# STM32F103ZET6.net
KiCad netlist of a schematic drawn in Altium Designer
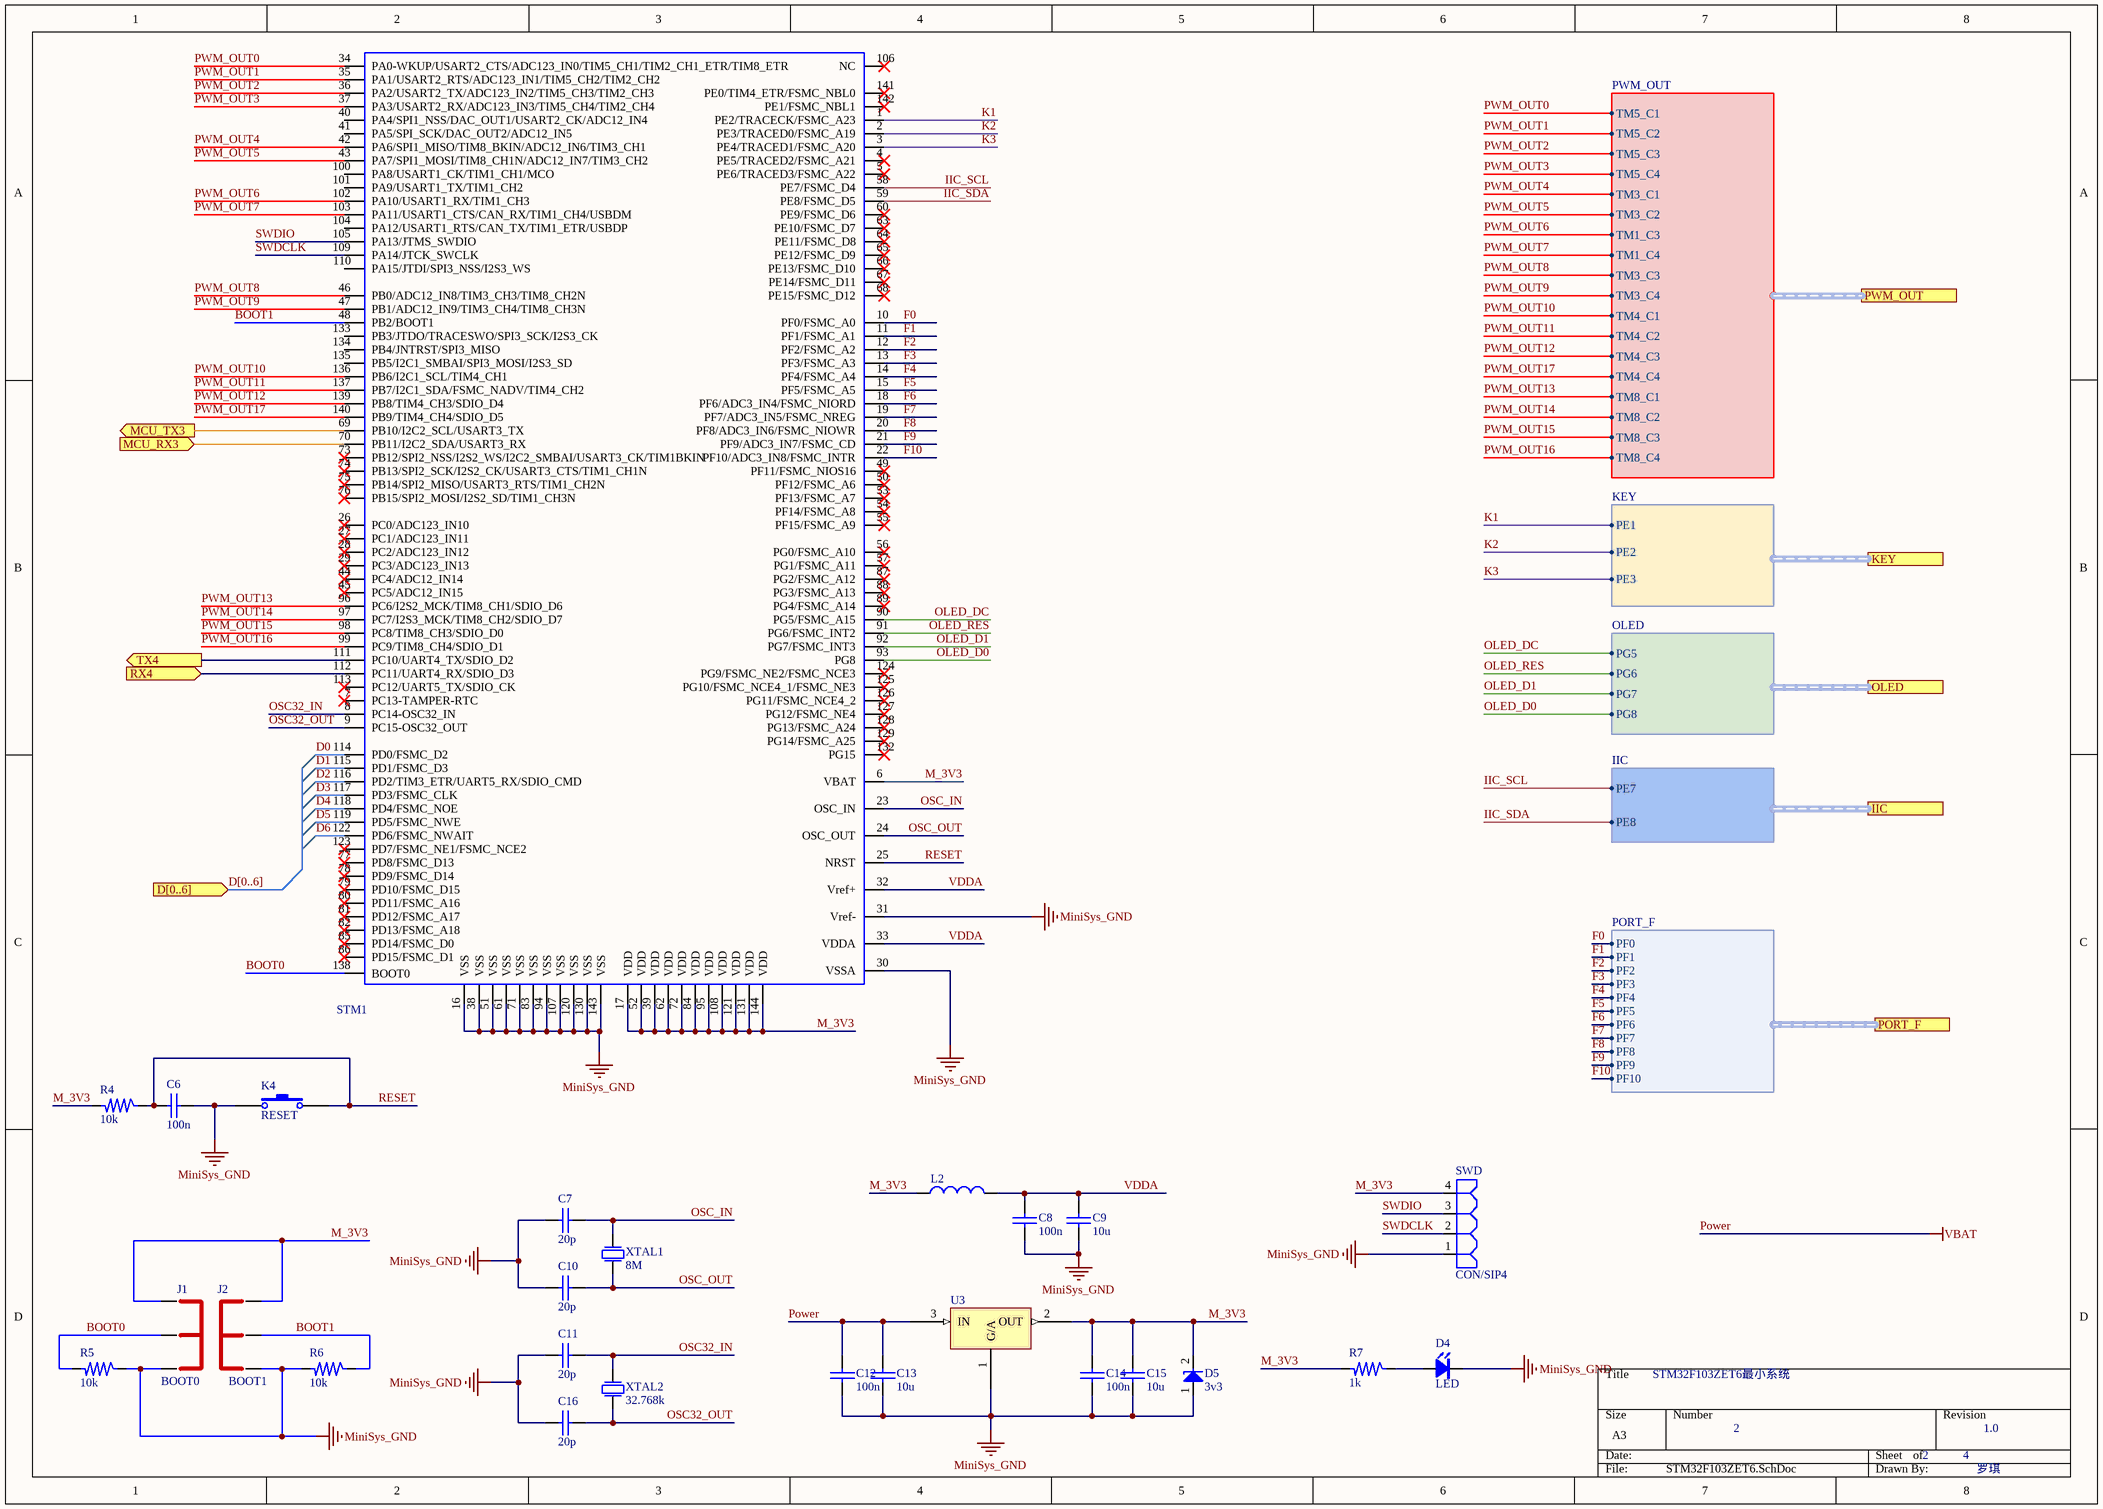
[diagram p0: STM32F103ZET6.SchDoc]

(export (version "E")
  (design (tool "Eeschema 10.0.6"))
  (components
    (comp (ref "C6")
      (value "100n")
      (footprint "C0402")
      (description "电容")
      (libsource (lib "LQ_Integrated_Library") (part "Capacitor"))
    )
    (comp (ref "C7")
      (value "20p")
      (footprint "C0402")
      (description "电容")
      (libsource (lib "LQ_Integrated_Library") (part "Capacitor"))
    )
    (comp (ref "C8")
      (value "100n")
      (footprint "C0402")
      (description "电容")
      (libsource (lib "LQ_Integrated_Library") (part "Capacitor"))
    )
    (comp (ref "C9")
      (value "10u")
      (footprint "C0402")
      (description "电容")
      (libsource (lib "LQ_Integrated_Library") (part "Capacitor"))
    )
    (comp (ref "C10")
      (value "20p")
      (footprint "C0402")
      (description "电容")
      (libsource (lib "LQ_Integrated_Library") (part "Capacitor"))
    )
    (comp (ref "C11")
      (value "20p")
      (footprint "C0402")
      (description "电容")
      (libsource (lib "LQ_Integrated_Library") (part "Capacitor"))
    )
    (comp (ref "C12")
      (value "100n")
      (footprint "C0402")
      (description "电容")
      (libsource (lib "LQ_Integrated_Library") (part "Capacitor"))
    )
    (comp (ref "C13")
      (value "10u")
      (footprint "C0402")
      (description "电容")
      (libsource (lib "LQ_Integrated_Library") (part "Capacitor"))
    )
    (comp (ref "C14")
      (value "100n")
      (footprint "C0402")
      (description "电容")
      (libsource (lib "LQ_Integrated_Library") (part "Capacitor"))
    )
    (comp (ref "C15")
      (value "10u")
      (footprint "C0402")
      (description "电容")
      (libsource (lib "LQ_Integrated_Library") (part "Capacitor"))
    )
    (comp (ref "C16")
      (value "20p")
      (footprint "C0402")
      (description "电容")
      (libsource (lib "LQ_Integrated_Library") (part "Capacitor"))
    )
    (comp (ref "D4")
      (value "LED")
      (footprint "LED0805TB")
      (libsource (lib "LQ_Integrated_Library") (part "LED"))
    )
    (comp (ref "D5")
      (value "3v3")
      (footprint "D1206")
      (libsource (lib "LQ_Integrated_Library") (part "DIODE稳压"))
    )
    (comp (ref "J1")
      (value "BOOT0")
      (footprint "Jumper3")
      (description "Jumper")
      (libsource (lib "LQ_Integrated_Library") (part "JUMPER3"))
    )
    (comp (ref "J2")
      (value "BOOT1")
      (footprint "Jumper3")
      (description "Jumper")
      (libsource (lib "LQ_Integrated_Library") (part "JUMPER3"))
    )
    (comp (ref "K4") (value "RESET") (footprint "按键-贴片-1") (libsource (lib "APPPCB") (part "按键")))
    (comp (ref "L2")
      (value "INDUCTOR")
      (footprint "L0805")
      (description "Inductor")
      (libsource (lib "LQ_Integrated_Library") (part "INDUCTOR"))
    )
    (comp (ref "R4")
      (value "10k")
      (footprint "R0805")
      (description "电阻")
      (libsource (lib "LQ_Integrated_Library") (part "Resistor"))
    )
    (comp (ref "R5")
      (value "10k")
      (footprint "R0805")
      (description "电阻")
      (libsource (lib "LQ_Integrated_Library") (part "Resistor"))
    )
    (comp (ref "R6")
      (value "10k")
      (footprint "R0805")
      (description "电阻")
      (libsource (lib "LQ_Integrated_Library") (part "Resistor"))
    )
    (comp (ref "R7")
      (value "1k")
      (footprint "R0805")
      (description "电阻")
      (libsource (lib "LQ_Integrated_Library") (part "Resistor"))
    )
    (comp (ref "STM1")
      (value "STM32F103ZET6")
      (footprint "STM32F103ZET6-1")
      (libsource (lib "APPPCB") (part "STM32F103ZET6"))
    )
    (comp (ref "SWD")
      (value "CON/SIP4")
      (footprint "HDR1X4")
      (libsource (lib "LQ_Integrated_Library") (part "CON/SIP4"))
    )
    (comp (ref "U3")
      (value "AMS1117-XX")
      (footprint "SOT223")
      (description "稳压芯片")
      (libsource (lib "LQ_Integrated_Library") (part "AMS1117-XX"))
    )
    (comp (ref "XTAL1")
      (value "8M")
      (footprint "XTAL-49/S_N")
      (description "CRYSTAL")
      (libsource (lib "LQ_Integrated_Library") (part "XTAL"))
    )
    (comp (ref "XTAL2")
      (value "32.768k")
      (footprint "XTAL_32.768")
      (description "CRYSTAL")
      (libsource (lib "LQ_Integrated_Library") (part "XTAL"))
    )
  )
  (nets
    (net (code "6") (name "/BOOT0") (class "Default")
      (node (ref "J1") (pin "2") (pinfunction "2_2") (pintype "passive"))
      (node (ref "R5") (pin "1") (pinfunction "1_1") (pintype "passive"))
      (node (ref "STM1") (pin "138") (pinfunction "BOOT0_138") (pintype "passive"))
    )
    (net (code "7") (name "/BOOT1") (class "Default")
      (node (ref "J2") (pin "2") (pinfunction "2_2") (pintype "passive"))
      (node (ref "R6") (pin "2") (pinfunction "2_2") (pintype "passive"))
      (node (ref "STM1") (pin "48") (pinfunction "PB2/BOOT1_48") (pintype "passive"))
    )
    (net (code "8") (name "/D0") (class "Default")
      (node (ref "STM1") (pin "114") (pinfunction "PD0/FSMC_D2_114") (pintype "passive"))
    )
    (net (code "9") (name "/D1") (class "Default")
      (node (ref "STM1") (pin "115") (pinfunction "PD1/FSMC_D3_115") (pintype "passive"))
    )
    (net (code "10") (name "/D2") (class "Default")
      (node (ref "STM1") (pin "116") (pinfunction "PD2/TIM3_ETR/UART5_RX/SDIO_CMD_116") (pintype "passive"))
    )
    (net (code "11") (name "/D3") (class "Default")
      (node (ref "STM1") (pin "117") (pinfunction "PD3/FSMC_CLK_117") (pintype "passive"))
    )
    (net (code "12") (name "/D4") (class "Default")
      (node (ref "STM1") (pin "118") (pinfunction "PD4/FSMC_NOE_118") (pintype "passive"))
    )
    (net (code "13") (name "/D5") (class "Default")
      (node (ref "STM1") (pin "119") (pinfunction "PD5/FSMC_NWE_119") (pintype "passive"))
    )
    (net (code "14") (name "/D6") (class "Default")
      (node (ref "STM1") (pin "122") (pinfunction "PD6/FSMC_NWAIT_122") (pintype "passive"))
    )
    (net (code "16") (name "/F0") (class "Default")
      (node (ref "STM1") (pin "10") (pinfunction "PF0/FSMC_A0_10") (pintype "passive"))
    )
    (net (code "17") (name "/F1") (class "Default")
      (node (ref "STM1") (pin "11") (pinfunction "PF1/FSMC_A1_11") (pintype "passive"))
    )
    (net (code "18") (name "/F2") (class "Default")
      (node (ref "STM1") (pin "12") (pinfunction "PF2/FSMC_A2_12") (pintype "passive"))
    )
    (net (code "19") (name "/F3") (class "Default")
      (node (ref "STM1") (pin "13") (pinfunction "PF3/FSMC_A3_13") (pintype "passive"))
    )
    (net (code "20") (name "/F4") (class "Default")
      (node (ref "STM1") (pin "14") (pinfunction "PF4/FSMC_A4_14") (pintype "passive"))
    )
    (net (code "21") (name "/F5") (class "Default")
      (node (ref "STM1") (pin "15") (pinfunction "PF5/FSMC_A5_15") (pintype "passive"))
    )
    (net (code "22") (name "/F6") (class "Default")
      (node (ref "STM1") (pin "18") (pinfunction "PF6/ADC3_IN4/FSMC_NIORD_18") (pintype "passive"))
    )
    (net (code "23") (name "/F7") (class "Default")
      (node (ref "STM1") (pin "19") (pinfunction "PF7/ADC3_IN5/FSMC_NREG_19") (pintype "passive"))
    )
    (net (code "24") (name "/F8") (class "Default")
      (node (ref "STM1") (pin "20") (pinfunction "PF8/ADC3_IN6/FSMC_NIOWR_20") (pintype "passive"))
    )
    (net (code "25") (name "/F9") (class "Default")
      (node (ref "STM1") (pin "21") (pinfunction "PF9/ADC3_IN7/FSMC_CD_21") (pintype "passive"))
    )
    (net (code "26") (name "/F10") (class "Default")
      (node (ref "STM1") (pin "22") (pinfunction "PF10/ADC3_IN8/FSMC_INTR_22") (pintype "passive"))
    )
    (net (code "27") (name "/IIC_SCL") (class "Default")
      (node (ref "STM1") (pin "58") (pinfunction "PE7/FSMC_D4_58") (pintype "passive"))
    )
    (net (code "28") (name "/IIC_SDA") (class "Default")
      (node (ref "STM1") (pin "59") (pinfunction "PE8/FSMC_D5_59") (pintype "passive"))
    )
    (net (code "29") (name "/K1") (class "Default")
      (node (ref "STM1") (pin "1") (pinfunction "PE2/TRACECK/FSMC_A23_1") (pintype "passive"))
    )
    (net (code "30") (name "/K2") (class "Default")
      (node (ref "STM1") (pin "2") (pinfunction "PE3/TRACED0/FSMC_A19_2") (pintype "passive"))
    )
    (net (code "31") (name "/K3") (class "Default")
      (node (ref "STM1") (pin "3") (pinfunction "PE4/TRACED1/FSMC_A20_3") (pintype "passive"))
    )
    (net (code "32") (name "/MCU_RX3") (class "Default")
      (node (ref "STM1") (pin "70") (pinfunction "PB11/I2C2_SDA/USART3_RX_70") (pintype "passive"))
    )
    (net (code "33") (name "/MCU_TX3") (class "Default")
      (node (ref "STM1") (pin "69") (pinfunction "PB10/I2C2_SCL/USART3_TX_69") (pintype "passive"))
    )
    (net (code "34") (name "/M_3V3") (class "Default")
      (node (ref "C14") (pin "2") (pinfunction "2_2") (pintype "passive"))
      (node (ref "C15") (pin "2") (pinfunction "2_2") (pintype "passive"))
      (node (ref "D5") (pin "2") (pintype "passive"))
      (node (ref "J1") (pin "1") (pinfunction "1_1") (pintype "passive"))
      (node (ref "J2") (pin "3") (pinfunction "3_3") (pintype "passive"))
      (node (ref "L2") (pin "1") (pinfunction "1_1") (pintype "passive"))
      (node (ref "R4") (pin "1") (pinfunction "1_1") (pintype "passive"))
      (node (ref "R7") (pin "1") (pinfunction "1_1") (pintype "passive"))
      (node (ref "STM1") (pin "108") (pinfunction "VDD_108") (pintype "passive"))
      (node (ref "STM1") (pin "121") (pinfunction "VDD_121") (pintype "passive"))
      (node (ref "STM1") (pin "131") (pinfunction "VDD_131") (pintype "passive"))
      (node (ref "STM1") (pin "144") (pinfunction "VDD_144") (pintype "passive"))
      (node (ref "STM1") (pin "17") (pinfunction "VDD_17") (pintype "passive"))
      (node (ref "STM1") (pin "39") (pinfunction "VDD_39") (pintype "passive"))
      (node (ref "STM1") (pin "52") (pinfunction "VDD_52") (pintype "passive"))
      (node (ref "STM1") (pin "6") (pinfunction "VBAT_6") (pintype "passive"))
      (node (ref "STM1") (pin "62") (pinfunction "VDD_62") (pintype "passive"))
      (node (ref "STM1") (pin "72") (pinfunction "VDD_72") (pintype "passive"))
      (node (ref "STM1") (pin "84") (pinfunction "VDD_84") (pintype "passive"))
      (node (ref "STM1") (pin "95") (pinfunction "VDD_95") (pintype "passive"))
      (node (ref "SWD") (pin "4") (pintype "passive"))
      (node (ref "U3") (pin "2") (pinfunction "OUT_2") (pintype "output"))
    )
    (net (code "35") (name "/OLED_D0") (class "Default")
      (node (ref "STM1") (pin "93") (pinfunction "PG8_93") (pintype "passive"))
    )
    (net (code "36") (name "/OLED_D1") (class "Default")
      (node (ref "STM1") (pin "92") (pinfunction "PG7/FSMC_INT3_92") (pintype "passive"))
    )
    (net (code "37") (name "/OLED_DC") (class "Default")
      (node (ref "STM1") (pin "90") (pinfunction "PG5/FSMC_A15_90") (pintype "passive"))
    )
    (net (code "38") (name "/OLED_RES") (class "Default")
      (node (ref "STM1") (pin "91") (pinfunction "PG6/FSMC_INT2_91") (pintype "passive"))
    )
    (net (code "39") (name "/OSC32_IN") (class "Default")
      (node (ref "C11") (pin "2") (pinfunction "2_2") (pintype "passive"))
      (node (ref "STM1") (pin "8") (pinfunction "PC14-OSC32_IN_8") (pintype "passive"))
      (node (ref "XTAL2") (pin "1") (pinfunction "P1_1") (pintype "passive"))
    )
    (net (code "40") (name "/OSC32_OUT") (class "Default")
      (node (ref "C16") (pin "2") (pinfunction "2_2") (pintype "passive"))
      (node (ref "STM1") (pin "9") (pinfunction "PC15-OSC32_OUT_9") (pintype "passive"))
      (node (ref "XTAL2") (pin "2") (pinfunction "P2_2") (pintype "passive"))
    )
    (net (code "41") (name "/OSC_IN") (class "Default")
      (node (ref "C7") (pin "2") (pinfunction "2_2") (pintype "passive"))
      (node (ref "STM1") (pin "23") (pinfunction "OSC_IN_23") (pintype "passive"))
      (node (ref "XTAL1") (pin "1") (pinfunction "P1_1") (pintype "passive"))
    )
    (net (code "42") (name "/OSC_OUT") (class "Default")
      (node (ref "C10") (pin "2") (pinfunction "2_2") (pintype "passive"))
      (node (ref "STM1") (pin "24") (pinfunction "OSC_OUT_24") (pintype "passive"))
      (node (ref "XTAL1") (pin "2") (pinfunction "P2_2") (pintype "passive"))
    )
    (net (code "43") (name "/PWM_OUT0") (class "Default")
      (node (ref "STM1") (pin "34") (pinfunction "PA0-WKUP/USART2_CTS/ADC123_IN0/TIM5_CH1/TIM2_CH1_ETR/TIM8_ETR_34") (pintype "passive"))
    )
    (net (code "44") (name "/PWM_OUT1") (class "Default")
      (node (ref "STM1") (pin "35") (pinfunction "PA1/USART2_RTS/ADC123_IN1/TIM5_CH2/TIM2_CH2_35") (pintype "passive"))
    )
    (net (code "45") (name "/PWM_OUT2") (class "Default")
      (node (ref "STM1") (pin "36") (pinfunction "PA2/USART2_TX/ADC123_IN2/TIM5_CH3/TIM2_CH3_36") (pintype "passive"))
    )
    (net (code "46") (name "/PWM_OUT3") (class "Default")
      (node (ref "STM1") (pin "37") (pinfunction "PA3/USART2_RX/ADC123_IN3/TIM5_CH4/TIM2_CH4_37") (pintype "passive"))
    )
    (net (code "47") (name "/PWM_OUT4") (class "Default")
      (node (ref "STM1") (pin "42") (pinfunction "PA6/SPI1_MISO/TIM8_BKIN/ADC12_IN6/TIM3_CH1_42") (pintype "passive"))
    )
    (net (code "48") (name "/PWM_OUT5") (class "Default")
      (node (ref "STM1") (pin "43") (pinfunction "PA7/SPI1_MOSI/TIM8_CH1N/ADC12_IN7/TIM3_CH2_43") (pintype "passive"))
    )
    (net (code "49") (name "/PWM_OUT6") (class "Default")
      (node (ref "STM1") (pin "102") (pinfunction "PA10/USART1_RX/TIM1_CH3_102") (pintype "passive"))
    )
    (net (code "50") (name "/PWM_OUT7") (class "Default")
      (node (ref "STM1") (pin "103") (pinfunction "PA11/USART1_CTS/CAN_RX/TIM1_CH4/USBDM_103") (pintype "passive"))
    )
    (net (code "51") (name "/PWM_OUT8") (class "Default")
      (node (ref "STM1") (pin "46") (pinfunction "PB0/ADC12_IN8/TIM3_CH3/TIM8_CH2N_46") (pintype "passive"))
    )
    (net (code "52") (name "/PWM_OUT9") (class "Default")
      (node (ref "STM1") (pin "47") (pinfunction "PB1/ADC12_IN9/TIM3_CH4/TIM8_CH3N_47") (pintype "passive"))
    )
    (net (code "53") (name "/PWM_OUT10") (class "Default")
      (node (ref "STM1") (pin "136") (pinfunction "PB6/I2C1_SCL/TIM4_CH1_136") (pintype "passive"))
    )
    (net (code "54") (name "/PWM_OUT11") (class "Default")
      (node (ref "STM1") (pin "137") (pinfunction "PB7/I2C1_SDA/FSMC_NADV/TIM4_CH2_137") (pintype "passive"))
    )
    (net (code "55") (name "/PWM_OUT12") (class "Default")
      (node (ref "STM1") (pin "139") (pinfunction "PB8/TIM4_CH3/SDIO_D4_139") (pintype "passive"))
    )
    (net (code "56") (name "/PWM_OUT13") (class "Default")
      (node (ref "STM1") (pin "96") (pinfunction "PC6/I2S2_MCK/TIM8_CH1/SDIO_D6_96") (pintype "passive"))
    )
    (net (code "57") (name "/PWM_OUT14") (class "Default")
      (node (ref "STM1") (pin "97") (pinfunction "PC7/I2S3_MCK/TIM8_CH2/SDIO_D7_97") (pintype "passive"))
    )
    (net (code "58") (name "/PWM_OUT15") (class "Default")
      (node (ref "STM1") (pin "98") (pinfunction "PC8/TIM8_CH3/SDIO_D0_98") (pintype "passive"))
    )
    (net (code "59") (name "/PWM_OUT16") (class "Default")
      (node (ref "STM1") (pin "99") (pinfunction "PC9/TIM8_CH4/SDIO_D1_99") (pintype "passive"))
    )
    (net (code "60") (name "/PWM_OUT17") (class "Default")
      (node (ref "STM1") (pin "140") (pinfunction "PB9/TIM4_CH4/SDIO_D5_140") (pintype "passive"))
    )
    (net (code "61") (name "/RESET") (class "Default")
      (node (ref "C6") (pin "1") (pinfunction "1_1") (pintype "passive"))
      (node (ref "K4") (pin "2") (pinfunction "2_2") (pintype "passive"))
      (node (ref "R4") (pin "2") (pinfunction "2_2") (pintype "passive"))
      (node (ref "STM1") (pin "25") (pinfunction "NRST_25") (pintype "passive"))
    )
    (net (code "62") (name "/RX4") (class "Default")
      (node (ref "STM1") (pin "112") (pinfunction "PC11/UART4_RX/SDIO_D3_112") (pintype "passive"))
    )
    (net (code "63") (name "/SWDCLK") (class "Default")
      (node (ref "STM1") (pin "109") (pinfunction "PA14/JTCK_SWCLK_109") (pintype "passive"))
      (node (ref "SWD") (pin "2") (pintype "passive"))
    )
    (net (code "64") (name "/SWDIO") (class "Default")
      (node (ref "STM1") (pin "105") (pinfunction "PA13/JTMS_SWDIO_105") (pintype "passive"))
      (node (ref "SWD") (pin "3") (pintype "passive"))
    )
    (net (code "65") (name "/TX4") (class "Default")
      (node (ref "STM1") (pin "111") (pinfunction "PC10/UART4_TX/SDIO_D2_111") (pintype "passive"))
    )
    (net (code "66") (name "/VDDA") (class "Default")
      (node (ref "C8") (pin "2") (pinfunction "2_2") (pintype "passive"))
      (node (ref "C9") (pin "2") (pinfunction "2_2") (pintype "passive"))
      (node (ref "L2") (pin "2") (pinfunction "2_2") (pintype "passive"))
      (node (ref "STM1") (pin "32") (pinfunction "Vref+_32") (pintype "passive"))
      (node (ref "STM1") (pin "33") (pinfunction "VDDA_33") (pintype "passive"))
    )
    (net (code "72") (name "MiniSys_GND") (class "Default")
      (node (ref "C10") (pin "1") (pinfunction "1_1") (pintype "passive"))
      (node (ref "C11") (pin "1") (pinfunction "1_1") (pintype "passive"))
      (node (ref "C12") (pin "1") (pinfunction "1_1") (pintype "passive"))
      (node (ref "C13") (pin "1") (pinfunction "1_1") (pintype "passive"))
      (node (ref "C14") (pin "1") (pinfunction "1_1") (pintype "passive"))
      (node (ref "C15") (pin "1") (pinfunction "1_1") (pintype "passive"))
      (node (ref "C16") (pin "1") (pinfunction "1_1") (pintype "passive"))
      (node (ref "C6") (pin "2") (pinfunction "2_2") (pintype "passive"))
      (node (ref "C7") (pin "1") (pinfunction "1_1") (pintype "passive"))
      (node (ref "C8") (pin "1") (pinfunction "1_1") (pintype "passive"))
      (node (ref "C9") (pin "1") (pinfunction "1_1") (pintype "passive"))
      (node (ref "D4") (pin "2") (pinfunction "K_2") (pintype "passive"))
      (node (ref "D5") (pin "1") (pintype "passive"))
      (node (ref "J1") (pin "3") (pinfunction "3_3") (pintype "passive"))
      (node (ref "J2") (pin "1") (pinfunction "1_1") (pintype "passive"))
      (node (ref "K4") (pin "1") (pinfunction "1_1") (pintype "passive"))
      (node (ref "R5") (pin "2") (pinfunction "2_2") (pintype "passive"))
      (node (ref "R6") (pin "1") (pinfunction "1_1") (pintype "passive"))
      (node (ref "STM1") (pin "107") (pinfunction "VSS_107") (pintype "passive"))
      (node (ref "STM1") (pin "120") (pinfunction "VSS_120") (pintype "passive"))
      (node (ref "STM1") (pin "130") (pinfunction "VSS_130") (pintype "passive"))
      (node (ref "STM1") (pin "143") (pinfunction "VSS_143") (pintype "passive"))
      (node (ref "STM1") (pin "16") (pinfunction "VSS_16") (pintype "passive"))
      (node (ref "STM1") (pin "30") (pinfunction "VSSA_30") (pintype "passive"))
      (node (ref "STM1") (pin "31") (pinfunction "Vref-_31") (pintype "passive"))
      (node (ref "STM1") (pin "38") (pinfunction "VSS_38") (pintype "passive"))
      (node (ref "STM1") (pin "51") (pinfunction "VSS_51") (pintype "passive"))
      (node (ref "STM1") (pin "61") (pinfunction "VSS_61") (pintype "passive"))
      (node (ref "STM1") (pin "71") (pinfunction "VSS_71") (pintype "passive"))
      (node (ref "STM1") (pin "83") (pinfunction "VSS_83") (pintype "passive"))
      (node (ref "STM1") (pin "94") (pinfunction "VSS_94") (pintype "passive"))
      (node (ref "SWD") (pin "1") (pintype "passive"))
      (node (ref "U3") (pin "1") (pinfunction "G/A_1") (pintype "passive"))
    )
    (net (code "73") (name "Net-(D4-A)") (class "Default")
      (node (ref "D4") (pin "1") (pinfunction "A_1") (pintype "passive"))
      (node (ref "R7") (pin "2") (pinfunction "2_2") (pintype "passive"))
    )
    (net (code "74") (name "VBAT") (class "Default")
      (node (ref "C12") (pin "2") (pinfunction "2_2") (pintype "passive"))
      (node (ref "C13") (pin "2") (pinfunction "2_2") (pintype "passive"))
      (node (ref "U3") (pin "3") (pinfunction "IN_3") (pintype "input"))
    )
    (net (code "75") (name "unconnected-(STM1-NC-Pad106)") (class "Default")
      (node (ref "STM1") (pin "106") (pinfunction "NC_106") (pintype "passive+no_connect"))
    )
    (net (code "76") (name "unconnected-(STM1-PA4{slash}SPI1_NSS{slash}DAC_OUT1{slash}USART2_CK{slash}ADC12_IN4-Pad40)") (class "Default")
      (node (ref "STM1") (pin "40") (pinfunction "PA4/SPI1_NSS/DAC_OUT1/USART2_CK/ADC12_IN4_40") (pintype "passive"))
    )
    (net (code "77") (name "unconnected-(STM1-PA5{slash}SPI_SCK{slash}DAC_OUT2{slash}ADC12_IN5-Pad41)") (class "Default")
      (node (ref "STM1") (pin "41") (pinfunction "PA5/SPI_SCK/DAC_OUT2/ADC12_IN5_41") (pintype "passive"))
    )
    (net (code "78") (name "unconnected-(STM1-PA8{slash}USART1_CK{slash}TIM1_CH1{slash}MCO-Pad100)") (class "Default")
      (node (ref "STM1") (pin "100") (pinfunction "PA8/USART1_CK/TIM1_CH1/MCO_100") (pintype "passive"))
    )
    (net (code "79") (name "unconnected-(STM1-PA9{slash}USART1_TX{slash}TIM1_CH2-Pad101)") (class "Default")
      (node (ref "STM1") (pin "101") (pinfunction "PA9/USART1_TX/TIM1_CH2_101") (pintype "passive"))
    )
    (net (code "80") (name "unconnected-(STM1-PA12{slash}USART1_RTS{slash}CAN_TX{slash}TIM1_ETR{slash}USBDP-Pad104)") (class "Default")
      (node (ref "STM1") (pin "104") (pinfunction "PA12/USART1_RTS/CAN_TX/TIM1_ETR/USBDP_104") (pintype "passive"))
    )
    (net (code "81") (name "unconnected-(STM1-PA15{slash}JTDI{slash}SPI3_NSS{slash}I2S3_WS-Pad110)") (class "Default")
      (node (ref "STM1") (pin "110") (pinfunction "PA15/JTDI/SPI3_NSS/I2S3_WS_110") (pintype "passive"))
    )
    (net (code "82") (name "unconnected-(STM1-PB3{slash}JTDO{slash}TRACESWO{slash}SPI3_SCK{slash}I2S3_CK-Pad133)") (class "Default")
      (node (ref "STM1") (pin "133") (pinfunction "PB3/JTDO/TRACESWO/SPI3_SCK/I2S3_CK_133") (pintype "passive"))
    )
    (net (code "83") (name "unconnected-(STM1-PB4{slash}JNTRST{slash}SPI3_MISO-Pad134)") (class "Default")
      (node (ref "STM1") (pin "134") (pinfunction "PB4/JNTRST/SPI3_MISO_134") (pintype "passive"))
    )
    (net (code "84") (name "unconnected-(STM1-PB5{slash}I2C1_SMBAI{slash}SPI3_MOSI{slash}I2S3_SD-Pad135)") (class "Default")
      (node (ref "STM1") (pin "135") (pinfunction "PB5/I2C1_SMBAI/SPI3_MOSI/I2S3_SD_135") (pintype "passive"))
    )
    (net (code "85") (name "unconnected-(STM1-PB12{slash}SPI2_NSS{slash}I2S2_WS{slash}I2C2_SMBAI{slash}USART3_CK{slash}TIM1BKIN-Pad73)") (class "Default")
      (node (ref "STM1") (pin "73") (pinfunction "PB12/SPI2_NSS/I2S2_WS/I2C2_SMBAI/USART3_CK/TIM1BKIN_73") (pintype "passive+no_connect"))
    )
    (net (code "86") (name "unconnected-(STM1-PB13{slash}SPI2_SCK{slash}I2S2_CK{slash}USART3_CTS{slash}TIM1_CH1N-Pad74)") (class "Default")
      (node (ref "STM1") (pin "74") (pinfunction "PB13/SPI2_SCK/I2S2_CK/USART3_CTS/TIM1_CH1N_74") (pintype "passive+no_connect"))
    )
    (net (code "87") (name "unconnected-(STM1-PB14{slash}SPI2_MISO{slash}USART3_RTS{slash}TIM1_CH2N-Pad75)") (class "Default")
      (node (ref "STM1") (pin "75") (pinfunction "PB14/SPI2_MISO/USART3_RTS/TIM1_CH2N_75") (pintype "passive+no_connect"))
    )
    (net (code "88") (name "unconnected-(STM1-PB15{slash}SPI2_MOSI{slash}I2S2_SD{slash}TIM1_CH3N-Pad76)") (class "Default")
      (node (ref "STM1") (pin "76") (pinfunction "PB15/SPI2_MOSI/I2S2_SD/TIM1_CH3N_76") (pintype "passive+no_connect"))
    )
    (net (code "89") (name "unconnected-(STM1-PC0{slash}ADC123_IN10-Pad26)") (class "Default")
      (node (ref "STM1") (pin "26") (pinfunction "PC0/ADC123_IN10_26") (pintype "passive+no_connect"))
    )
    (net (code "90") (name "unconnected-(STM1-PC1{slash}ADC123_IN11-Pad27)") (class "Default")
      (node (ref "STM1") (pin "27") (pinfunction "PC1/ADC123_IN11_27") (pintype "passive+no_connect"))
    )
    (net (code "91") (name "unconnected-(STM1-PC2{slash}ADC123_IN12-Pad28)") (class "Default")
      (node (ref "STM1") (pin "28") (pinfunction "PC2/ADC123_IN12_28") (pintype "passive+no_connect"))
    )
    (net (code "92") (name "unconnected-(STM1-PC3{slash}ADC123_IN13-Pad29)") (class "Default")
      (node (ref "STM1") (pin "29") (pinfunction "PC3/ADC123_IN13_29") (pintype "passive+no_connect"))
    )
    (net (code "93") (name "unconnected-(STM1-PC4{slash}ADC12_IN14-Pad44)") (class "Default")
      (node (ref "STM1") (pin "44") (pinfunction "PC4/ADC12_IN14_44") (pintype "passive+no_connect"))
    )
    (net (code "94") (name "unconnected-(STM1-PC5{slash}ADC12_IN15-Pad45)") (class "Default")
      (node (ref "STM1") (pin "45") (pinfunction "PC5/ADC12_IN15_45") (pintype "passive+no_connect"))
    )
    (net (code "95") (name "unconnected-(STM1-PC12{slash}UART5_TX{slash}SDIO_CK-Pad113)") (class "Default")
      (node (ref "STM1") (pin "113") (pinfunction "PC12/UART5_TX/SDIO_CK_113") (pintype "passive+no_connect"))
    )
    (net (code "96") (name "unconnected-(STM1-PC13-TAMPER-RTC-Pad7)") (class "Default")
      (node (ref "STM1") (pin "7") (pinfunction "PC13-TAMPER-RTC_7") (pintype "passive+no_connect"))
    )
    (net (code "97") (name "unconnected-(STM1-PD7{slash}FSMC_NE1{slash}FSMC_NCE2-Pad123)") (class "Default")
      (node (ref "STM1") (pin "123") (pinfunction "PD7/FSMC_NE1/FSMC_NCE2_123") (pintype "passive+no_connect"))
    )
    (net (code "98") (name "unconnected-(STM1-PD8{slash}FSMC_D13-Pad77)") (class "Default")
      (node (ref "STM1") (pin "77") (pinfunction "PD8/FSMC_D13_77") (pintype "passive+no_connect"))
    )
    (net (code "99") (name "unconnected-(STM1-PD9{slash}FSMC_D14-Pad78)") (class "Default")
      (node (ref "STM1") (pin "78") (pinfunction "PD9/FSMC_D14_78") (pintype "passive+no_connect"))
    )
    (net (code "100") (name "unconnected-(STM1-PD10{slash}FSMC_D15-Pad79)") (class "Default")
      (node (ref "STM1") (pin "79") (pinfunction "PD10/FSMC_D15_79") (pintype "passive+no_connect"))
    )
    (net (code "101") (name "unconnected-(STM1-PD11{slash}FSMC_A16-Pad80)") (class "Default")
      (node (ref "STM1") (pin "80") (pinfunction "PD11/FSMC_A16_80") (pintype "passive+no_connect"))
    )
    (net (code "102") (name "unconnected-(STM1-PD12{slash}FSMC_A17-Pad81)") (class "Default")
      (node (ref "STM1") (pin "81") (pinfunction "PD12/FSMC_A17_81") (pintype "passive+no_connect"))
    )
    (net (code "103") (name "unconnected-(STM1-PD13{slash}FSMC_A18-Pad82)") (class "Default")
      (node (ref "STM1") (pin "82") (pinfunction "PD13/FSMC_A18_82") (pintype "passive+no_connect"))
    )
    (net (code "104") (name "unconnected-(STM1-PD14{slash}FSMC_D0-Pad85)") (class "Default")
      (node (ref "STM1") (pin "85") (pinfunction "PD14/FSMC_D0_85") (pintype "passive+no_connect"))
    )
    (net (code "105") (name "unconnected-(STM1-PD15{slash}FSMC_D1-Pad86)") (class "Default")
      (node (ref "STM1") (pin "86") (pinfunction "PD15/FSMC_D1_86") (pintype "passive+no_connect"))
    )
    (net (code "106") (name "unconnected-(STM1-PE0{slash}TIM4_ETR{slash}FSMC_NBL0-Pad141)") (class "Default")
      (node (ref "STM1") (pin "141") (pinfunction "PE0/TIM4_ETR/FSMC_NBL0_141") (pintype "passive+no_connect"))
    )
    (net (code "107") (name "unconnected-(STM1-PE1{slash}FSMC_NBL1-Pad142)") (class "Default")
      (node (ref "STM1") (pin "142") (pinfunction "PE1/FSMC_NBL1_142") (pintype "passive+no_connect"))
    )
    (net (code "108") (name "unconnected-(STM1-PE5{slash}TRACED2{slash}FSMC_A21-Pad4)") (class "Default")
      (node (ref "STM1") (pin "4") (pinfunction "PE5/TRACED2/FSMC_A21_4") (pintype "passive+no_connect"))
    )
    (net (code "109") (name "unconnected-(STM1-PE6{slash}TRACED3{slash}FSMC_A22-Pad5)") (class "Default")
      (node (ref "STM1") (pin "5") (pinfunction "PE6/TRACED3/FSMC_A22_5") (pintype "passive+no_connect"))
    )
    (net (code "110") (name "unconnected-(STM1-PE9{slash}FSMC_D6-Pad60)") (class "Default")
      (node (ref "STM1") (pin "60") (pinfunction "PE9/FSMC_D6_60") (pintype "passive+no_connect"))
    )
    (net (code "111") (name "unconnected-(STM1-PE10{slash}FSMC_D7-Pad63)") (class "Default")
      (node (ref "STM1") (pin "63") (pinfunction "PE10/FSMC_D7_63") (pintype "passive+no_connect"))
    )
    (net (code "112") (name "unconnected-(STM1-PE11{slash}FSMC_D8-Pad64)") (class "Default")
      (node (ref "STM1") (pin "64") (pinfunction "PE11/FSMC_D8_64") (pintype "passive+no_connect"))
    )
    (net (code "113") (name "unconnected-(STM1-PE12{slash}FSMC_D9-Pad65)") (class "Default")
      (node (ref "STM1") (pin "65") (pinfunction "PE12/FSMC_D9_65") (pintype "passive+no_connect"))
    )
    (net (code "114") (name "unconnected-(STM1-PE13{slash}FSMC_D10-Pad66)") (class "Default")
      (node (ref "STM1") (pin "66") (pinfunction "PE13/FSMC_D10_66") (pintype "passive+no_connect"))
    )
    (net (code "115") (name "unconnected-(STM1-PE14{slash}FSMC_D11-Pad67)") (class "Default")
      (node (ref "STM1") (pin "67") (pinfunction "PE14/FSMC_D11_67") (pintype "passive+no_connect"))
    )
    (net (code "116") (name "unconnected-(STM1-PE15{slash}FSMC_D12-Pad68)") (class "Default")
      (node (ref "STM1") (pin "68") (pinfunction "PE15/FSMC_D12_68") (pintype "passive+no_connect"))
    )
    (net (code "117") (name "unconnected-(STM1-PF11{slash}FSMC_NIOS16-Pad49)") (class "Default")
      (node (ref "STM1") (pin "49") (pinfunction "PF11/FSMC_NIOS16_49") (pintype "passive+no_connect"))
    )
    (net (code "118") (name "unconnected-(STM1-PF12{slash}FSMC_A6-Pad50)") (class "Default")
      (node (ref "STM1") (pin "50") (pinfunction "PF12/FSMC_A6_50") (pintype "passive+no_connect"))
    )
    (net (code "119") (name "unconnected-(STM1-PF13{slash}FSMC_A7-Pad53)") (class "Default")
      (node (ref "STM1") (pin "53") (pinfunction "PF13/FSMC_A7_53") (pintype "passive+no_connect"))
    )
    (net (code "120") (name "unconnected-(STM1-PF14{slash}FSMC_A8-Pad54)") (class "Default")
      (node (ref "STM1") (pin "54") (pinfunction "PF14/FSMC_A8_54") (pintype "passive+no_connect"))
    )
    (net (code "121") (name "unconnected-(STM1-PF15{slash}FSMC_A9-Pad55)") (class "Default")
      (node (ref "STM1") (pin "55") (pinfunction "PF15/FSMC_A9_55") (pintype "passive+no_connect"))
    )
    (net (code "122") (name "unconnected-(STM1-PG0{slash}FSMC_A10-Pad56)") (class "Default")
      (node (ref "STM1") (pin "56") (pinfunction "PG0/FSMC_A10_56") (pintype "passive+no_connect"))
    )
    (net (code "123") (name "unconnected-(STM1-PG1{slash}FSMC_A11-Pad57)") (class "Default")
      (node (ref "STM1") (pin "57") (pinfunction "PG1/FSMC_A11_57") (pintype "passive+no_connect"))
    )
    (net (code "124") (name "unconnected-(STM1-PG2{slash}FSMC_A12-Pad87)") (class "Default")
      (node (ref "STM1") (pin "87") (pinfunction "PG2/FSMC_A12_87") (pintype "passive+no_connect"))
    )
    (net (code "125") (name "unconnected-(STM1-PG3{slash}FSMC_A13-Pad88)") (class "Default")
      (node (ref "STM1") (pin "88") (pinfunction "PG3/FSMC_A13_88") (pintype "passive+no_connect"))
    )
    (net (code "126") (name "unconnected-(STM1-PG4{slash}FSMC_A14-Pad89)") (class "Default")
      (node (ref "STM1") (pin "89") (pinfunction "PG4/FSMC_A14_89") (pintype "passive+no_connect"))
    )
    (net (code "127") (name "unconnected-(STM1-PG9{slash}FSMC_NE2{slash}FSMC_NCE3-Pad124)") (class "Default")
      (node (ref "STM1") (pin "124") (pinfunction "PG9/FSMC_NE2/FSMC_NCE3_124") (pintype "passive+no_connect"))
    )
    (net (code "128") (name "unconnected-(STM1-PG10{slash}FSMC_NCE4_1{slash}FSMC_NE3-Pad125)") (class "Default")
      (node (ref "STM1") (pin "125") (pinfunction "PG10/FSMC_NCE4_1/FSMC_NE3_125") (pintype "passive+no_connect"))
    )
    (net (code "129") (name "unconnected-(STM1-PG11{slash}FSMC_NCE4_2-Pad126)") (class "Default")
      (node (ref "STM1") (pin "126") (pinfunction "PG11/FSMC_NCE4_2_126") (pintype "passive+no_connect"))
    )
    (net (code "130") (name "unconnected-(STM1-PG12{slash}FSMC_NE4-Pad127)") (class "Default")
      (node (ref "STM1") (pin "127") (pinfunction "PG12/FSMC_NE4_127") (pintype "passive+no_connect"))
    )
    (net (code "131") (name "unconnected-(STM1-PG13{slash}FSMC_A24-Pad128)") (class "Default")
      (node (ref "STM1") (pin "128") (pinfunction "PG13/FSMC_A24_128") (pintype "passive+no_connect"))
    )
    (net (code "132") (name "unconnected-(STM1-PG14{slash}FSMC_A25-Pad129)") (class "Default")
      (node (ref "STM1") (pin "129") (pinfunction "PG14/FSMC_A25_129") (pintype "passive+no_connect"))
    )
    (net (code "133") (name "unconnected-(STM1-PG15-Pad132)") (class "Default")
      (node (ref "STM1") (pin "132") (pinfunction "PG15_132") (pintype "passive+no_connect"))
    )
  )
)
